# Uc_Ticketing_Master.net
KiCad netlist of a schematic drawn in Altium Designer
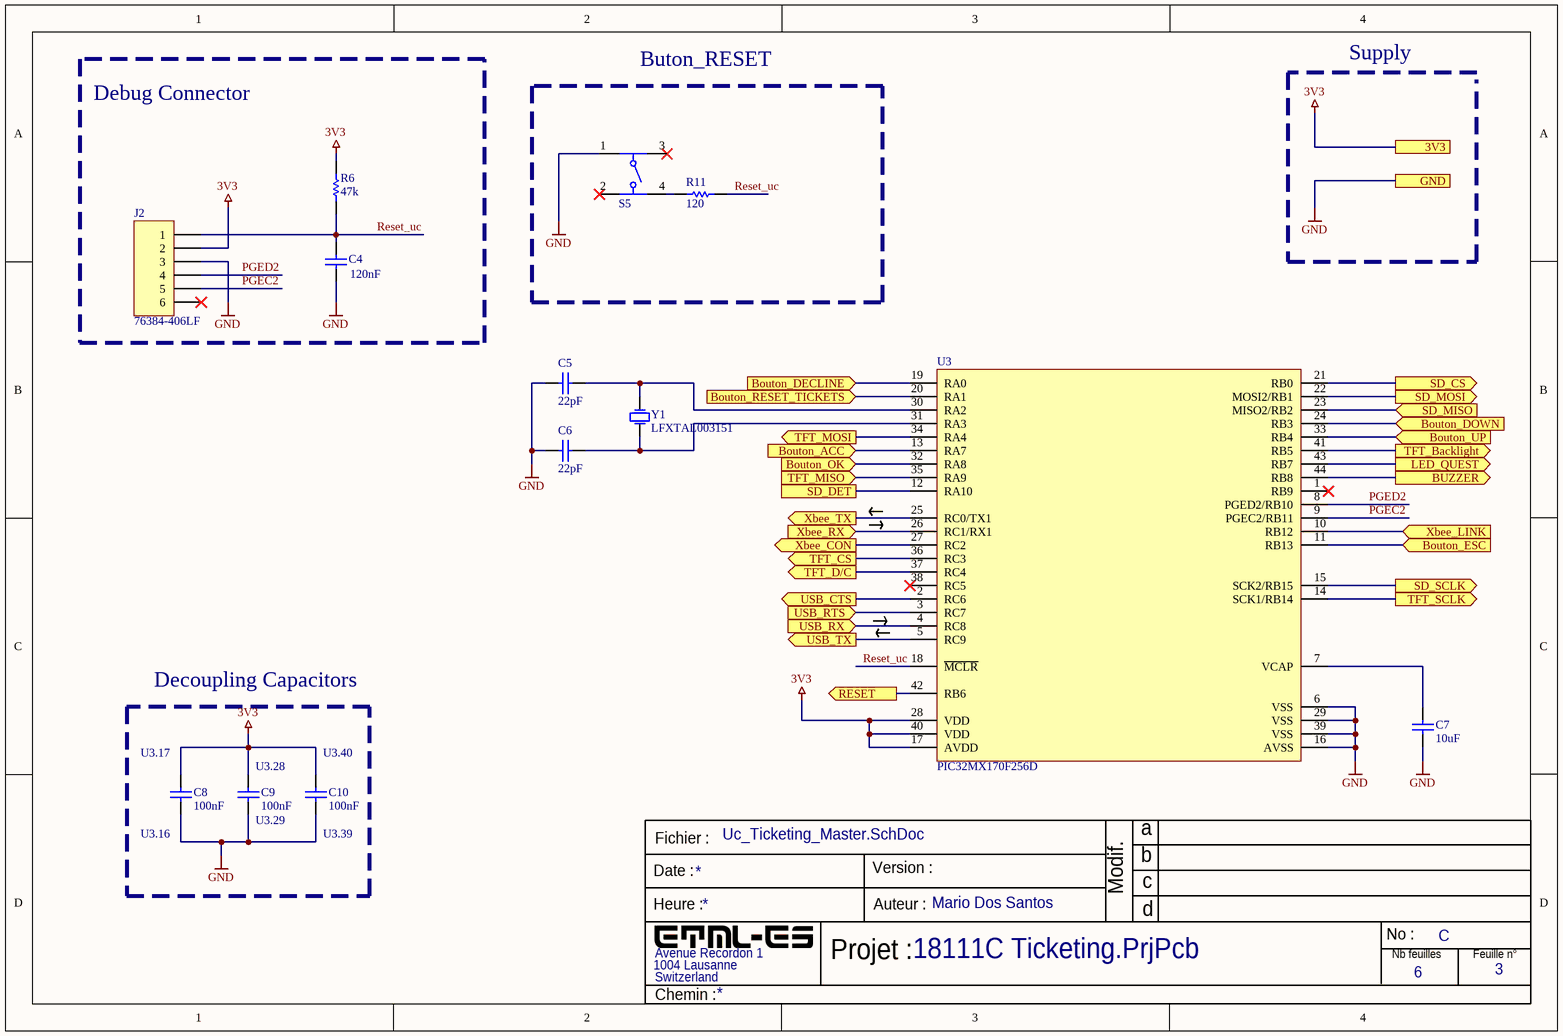
[diagram p0: Uc_Ticketing_Master.SchDoc]

(export (version "E")
  (design (tool "Eeschema 10.0.6"))
  (components
    (comp (ref "C4")
      (value "120nF")
      (footprint "6-0805_N")
      (description "Capacitor")
      (libsource (lib "Miscellaneous Devices") (part "Cap"))
    )
    (comp (ref "C5")
      (value "22pF")
      (footprint "6-0805_N")
      (description "VJ0805Y104KNAAT")
      (libsource (lib "2126_AffichageMatriciel") (part "CMP-2007-03167-1"))
    )
    (comp (ref "C6")
      (value "22pF")
      (footprint "6-0805_N")
      (description "VJ0805Y104KNAAT")
      (libsource (lib "2126_AffichageMatriciel") (part "CMP-2007-03167-1"))
    )
    (comp (ref "C7")
      (value "10uF")
      (footprint "6-0805_N")
      (description "Capacitor")
      (libsource (lib "Miscellaneous Devices") (part "Cap"))
    )
    (comp (ref "C8")
      (value "100nF")
      (footprint "6-0805_N")
      (description "Capacitor")
      (libsource (lib "Miscellaneous Devices") (part "Cap"))
    )
    (comp (ref "C9")
      (value "100nF")
      (footprint "6-0805_N")
      (description "Capacitor")
      (libsource (lib "Miscellaneous Devices") (part "Cap"))
    )
    (comp (ref "C10")
      (value "100nF")
      (footprint "6-0805_N")
      (description "Capacitor")
      (libsource (lib "Miscellaneous Devices") (part "Cap"))
    )
    (comp (ref "J2")
      (value "76384-406LF")
      (footprint "76384-406LF")
      (description "Header, 6-Pin")
      (fields (field (name "PUBLISHER") "Altium Limited"))
      (libsource (lib "Miscellaneous Connectors") (part "Header 6"))
    )
    (comp (ref "R6")
      (value "47k")
      (footprint "RESC0805(2012)_L")
      (description "100K 0.125W 5% 0805 (2012 Metric)  SMD")
      (libsource (lib "Altium Content Vault") (part "CMP-1013-00122-1"))
    )
    (comp (ref "R11")
      (value "120")
      (footprint "RESC0805(2012)_L")
      (description "100K 0.125W 5% 0805 (2012 Metric)  SMD")
      (libsource (lib "Altium Content Vault") (part "CMP-1013-00122-1"))
    )
    (comp (ref "S5")
      (value "430182050816")
      (footprint "430182050816")
      (description "6x6mm SMD Tact Switch WS-TASV, height 5 mm, 160 gf")
      (libsource (lib "ALTIUM-WS-TASV-rev17b") (part "430182050816"))
    )
    (comp (ref "U3")
      (value "PIC32MX170F256D")
      (footprint "MCHP-TQFP-PT44_N")
      (libsource (lib "PCB_Ticketing_Master") (part "MCHP-PIC32MX2XXFXXXD-TQFP-44"))
    )
    (comp (ref "Y1")
      (value "LFXTAL003151")
      (footprint "LFXTAL003151REEL")
      (description "Crystal or Oscillator")
      (libsource (lib "2126_AffichageMatriciel") (part "LFXTAL003151REEL"))
    )
  )
  (nets
    (net (code "1") (name "/BUZZER") (class "Default")
      (node (ref "U3") (pin "44") (pinfunction "RB8_44") (pintype "passive"))
    )
    (net (code "2") (name "/Bouton_ACC") (class "Default")
      (node (ref "U3") (pin "13") (pinfunction "RA7_13") (pintype "passive"))
    )
    (net (code "3") (name "/Bouton_DECLINE") (class "Default")
      (node (ref "U3") (pin "19") (pinfunction "RA0_19") (pintype "passive"))
    )
    (net (code "4") (name "/Bouton_DOWN") (class "Default")
      (node (ref "U3") (pin "24") (pinfunction "RB3_24") (pintype "passive"))
    )
    (net (code "5") (name "/Bouton_ESC") (class "Default")
      (node (ref "U3") (pin "11") (pinfunction "RB13_11") (pintype "passive"))
    )
    (net (code "6") (name "/Bouton_OK") (class "Default")
      (node (ref "U3") (pin "32") (pinfunction "RA8_32") (pintype "passive"))
    )
    (net (code "7") (name "/Bouton_RESET_TICKETS") (class "Default")
      (node (ref "U3") (pin "20") (pinfunction "RA1_20") (pintype "passive"))
    )
    (net (code "8") (name "/Bouton_UP") (class "Default")
      (node (ref "U3") (pin "33") (pinfunction "RB4_33") (pintype "passive"))
    )
    (net (code "9") (name "/LED_QUEST") (class "Default")
      (node (ref "U3") (pin "43") (pinfunction "RB7_43") (pintype "passive"))
    )
    (net (code "10") (name "/PGEC2") (class "Default")
      (node (ref "J2") (pin "5") (pinfunction "5_5") (pintype "passive"))
      (node (ref "U3") (pin "9") (pinfunction "PGEC2/RB11_9") (pintype "passive"))
    )
    (net (code "11") (name "/PGED2") (class "Default")
      (node (ref "J2") (pin "4") (pinfunction "4_4") (pintype "passive"))
      (node (ref "U3") (pin "8") (pinfunction "PGED2/RB10_8") (pintype "passive"))
    )
    (net (code "12") (name "/RESET") (class "Default")
      (node (ref "U3") (pin "42") (pinfunction "RB6_42") (pintype "passive"))
    )
    (net (code "13") (name "/Reset_uc") (class "Default")
      (node (ref "C4") (pin "2") (pinfunction "2_2") (pintype "passive"))
      (node (ref "J2") (pin "1") (pinfunction "1_1") (pintype "passive"))
      (node (ref "R11") (pin "2") (pinfunction "2_2") (pintype "passive"))
      (node (ref "R6") (pin "2") (pinfunction "2_2") (pintype "passive"))
      (node (ref "U3") (pin "18") (pinfunction "~{MCLR}_18") (pintype "passive"))
    )
    (net (code "14") (name "/SD_CS") (class "Default")
      (node (ref "U3") (pin "21") (pinfunction "RB0_21") (pintype "passive"))
    )
    (net (code "15") (name "/SD_DET") (class "Default")
      (node (ref "U3") (pin "12") (pinfunction "RA10_12") (pintype "passive"))
    )
    (net (code "16") (name "/SD_MISO") (class "Default")
      (node (ref "U3") (pin "23") (pinfunction "MISO2/RB2_23") (pintype "passive"))
    )
    (net (code "17") (name "/SD_MOSI") (class "Default")
      (node (ref "U3") (pin "22") (pinfunction "MOSI2/RB1_22") (pintype "passive"))
    )
    (net (code "18") (name "/SD_SCLK") (class "Default")
      (node (ref "U3") (pin "15") (pinfunction "SCK2/RB15_15") (pintype "passive"))
    )
    (net (code "19") (name "/TFT_Backlight") (class "Default")
      (node (ref "U3") (pin "41") (pinfunction "RB5_41") (pintype "passive"))
    )
    (net (code "20") (name "/TFT_CS") (class "Default")
      (node (ref "U3") (pin "36") (pinfunction "RC3_36") (pintype "passive"))
    )
    (net (code "21") (name "/TFT_D{slash}C") (class "Default")
      (node (ref "U3") (pin "37") (pinfunction "RC4_37") (pintype "passive"))
    )
    (net (code "22") (name "/TFT_MISO") (class "Default")
      (node (ref "U3") (pin "35") (pinfunction "RA9_35") (pintype "passive"))
    )
    (net (code "23") (name "/TFT_MOSI") (class "Default")
      (node (ref "U3") (pin "34") (pinfunction "RA4_34") (pintype "passive"))
    )
    (net (code "24") (name "/TFT_SCLK") (class "Default")
      (node (ref "U3") (pin "14") (pinfunction "SCK1/RB14_14") (pintype "passive"))
    )
    (net (code "25") (name "/USB_CTS") (class "Default")
      (node (ref "U3") (pin "2") (pinfunction "RC6_2") (pintype "passive"))
    )
    (net (code "26") (name "/USB_RTS") (class "Default")
      (node (ref "U3") (pin "3") (pinfunction "RC7_3") (pintype "passive"))
    )
    (net (code "27") (name "/USB_RX") (class "Default")
      (node (ref "U3") (pin "4") (pinfunction "RC8_4") (pintype "passive"))
    )
    (net (code "28") (name "/USB_TX") (class "Default")
      (node (ref "U3") (pin "5") (pinfunction "RC9_5") (pintype "passive"))
    )
    (net (code "29") (name "/Xbee_CON") (class "Default")
      (node (ref "U3") (pin "27") (pinfunction "RC2_27") (pintype "passive"))
    )
    (net (code "30") (name "/Xbee_LINK") (class "Default")
      (node (ref "U3") (pin "10") (pinfunction "RB12_10") (pintype "passive"))
    )
    (net (code "31") (name "/Xbee_RX") (class "Default")
      (node (ref "U3") (pin "26") (pinfunction "RC1/RX1_26") (pintype "passive"))
    )
    (net (code "32") (name "/Xbee_TX") (class "Default")
      (node (ref "U3") (pin "25") (pinfunction "RC0/TX1_25") (pintype "passive"))
    )
    (net (code "33") (name "3V3") (class "Default")
      (node (ref "C10") (pin "2") (pinfunction "2_2") (pintype "passive"))
      (node (ref "C8") (pin "2") (pinfunction "2_2") (pintype "passive"))
      (node (ref "C9") (pin "2") (pinfunction "2_2") (pintype "passive"))
      (node (ref "J2") (pin "2") (pinfunction "2_2") (pintype "passive"))
      (node (ref "R6") (pin "1") (pinfunction "1_1") (pintype "passive"))
      (node (ref "U3") (pin "17") (pinfunction "AVDD_17") (pintype "passive"))
      (node (ref "U3") (pin "28") (pinfunction "VDD_28") (pintype "passive"))
      (node (ref "U3") (pin "40") (pinfunction "VDD_40") (pintype "passive"))
    )
    (net (code "34") (name "GND") (class "Default")
      (node (ref "C10") (pin "1") (pinfunction "1_1") (pintype "passive"))
      (node (ref "C4") (pin "1") (pinfunction "1_1") (pintype "passive"))
      (node (ref "C5") (pin "1") (pinfunction "1_1") (pintype "passive"))
      (node (ref "C6") (pin "1") (pinfunction "1_1") (pintype "passive"))
      (node (ref "C7") (pin "1") (pinfunction "1_1") (pintype "passive"))
      (node (ref "C8") (pin "1") (pinfunction "1_1") (pintype "passive"))
      (node (ref "C9") (pin "1") (pinfunction "1_1") (pintype "passive"))
      (node (ref "J2") (pin "3") (pinfunction "3_3") (pintype "passive"))
      (node (ref "S5") (pin "1") (pinfunction "1_1") (pintype "passive"))
      (node (ref "U3") (pin "16") (pinfunction "AVSS_16") (pintype "passive"))
      (node (ref "U3") (pin "29") (pinfunction "VSS_29") (pintype "passive"))
      (node (ref "U3") (pin "39") (pinfunction "VSS_39") (pintype "passive"))
      (node (ref "U3") (pin "6") (pinfunction "VSS_6") (pintype "passive"))
    )
    (net (code "35") (name "Net-(R11-Pad1)") (class "Default")
      (node (ref "R11") (pin "1") (pinfunction "1_1") (pintype "passive"))
      (node (ref "S5") (pin "4") (pinfunction "4_4") (pintype "passive"))
    )
    (net (code "36") (name "Net-(U3-RA2)") (class "Default")
      (node (ref "C5") (pin "2") (pinfunction "2_2") (pintype "passive"))
      (node (ref "U3") (pin "30") (pinfunction "RA2_30") (pintype "passive"))
      (node (ref "Y1") (pin "1") (pinfunction "1_1") (pintype "passive"))
    )
    (net (code "37") (name "Net-(U3-RA3)") (class "Default")
      (node (ref "C6") (pin "2") (pinfunction "2_2") (pintype "passive"))
      (node (ref "U3") (pin "31") (pinfunction "RA3_31") (pintype "passive"))
      (node (ref "Y1") (pin "2") (pinfunction "2_2") (pintype "passive"))
    )
    (net (code "38") (name "Net-(U3-VCAP)") (class "Default")
      (node (ref "C7") (pin "2") (pinfunction "2_2") (pintype "passive"))
      (node (ref "U3") (pin "7") (pinfunction "VCAP_7") (pintype "passive"))
    )
    (net (code "39") (name "unconnected-(J2-Pad6)") (class "Default")
      (node (ref "J2") (pin "6") (pinfunction "6_6") (pintype "passive+no_connect"))
    )
    (net (code "40") (name "unconnected-(S5-Pad2)") (class "Default")
      (node (ref "S5") (pin "2") (pinfunction "2_2") (pintype "passive+no_connect"))
    )
    (net (code "41") (name "unconnected-(S5-Pad3)") (class "Default")
      (node (ref "S5") (pin "3") (pinfunction "3_3") (pintype "passive+no_connect"))
    )
    (net (code "42") (name "unconnected-(U3-RB9-Pad1)") (class "Default")
      (node (ref "U3") (pin "1") (pinfunction "RB9_1") (pintype "passive+no_connect"))
    )
    (net (code "43") (name "unconnected-(U3-RC5-Pad38)") (class "Default")
      (node (ref "U3") (pin "38") (pinfunction "RC5_38") (pintype "passive+no_connect"))
    )
  )
)
